# pcb_1.net
KiCad netlist of a schematic drawn in EAGLE
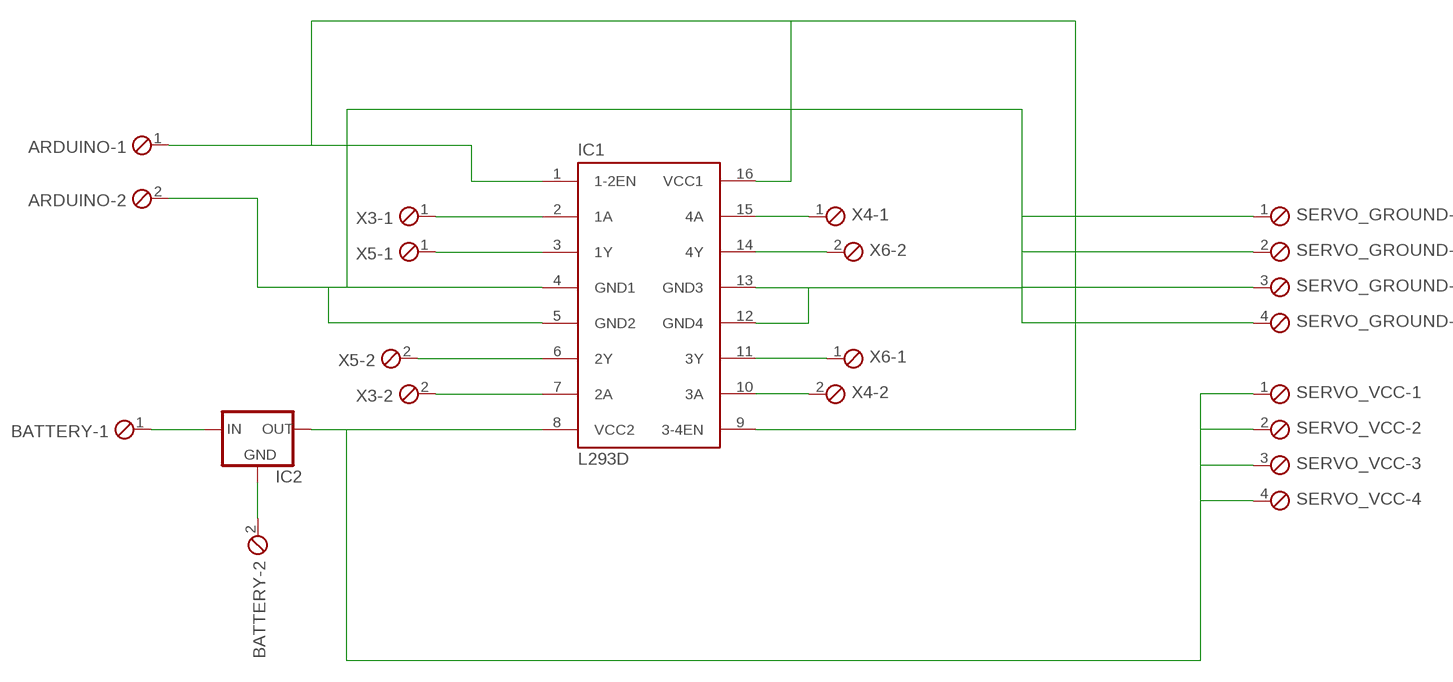
[diagram p0: schematic, sheet 1]

(export (version "E")
  (design (tool "Eeschema 10.0.6"))
  (components
    (comp (ref "ARDUINO")
      (value "MPT2")
      (footprint "eagle-import:2POL254")
      (libsource (lib "eagle-import") (part "MPT2"))
    )
    (comp (ref "BATTERY")
      (value "MPT2")
      (footprint "eagle-import:2POL254")
      (libsource (lib "eagle-import") (part "MPT2"))
    )
    (comp (ref "IC1")
      (value "L293D")
      (footprint "eagle-import:DIL16")
      (libsource (lib "eagle-import") (part "L293D"))
    )
    (comp (ref "IC2")
      (value "78MXXS")
      (footprint "eagle-import:78MXXS")
      (libsource (lib "eagle-import") (part "78MXXS"))
    )
    (comp (ref "SERVO_GROUND")
      (value "MPT4")
      (footprint "eagle-import:4POL254")
      (libsource (lib "eagle-import") (part "MPT4"))
    )
    (comp (ref "SERVO_VCC")
      (value "MPT4")
      (footprint "eagle-import:4POL254")
      (libsource (lib "eagle-import") (part "MPT4"))
    )
    (comp (ref "X3")
      (value "MPT2")
      (footprint "eagle-import:2POL254")
      (libsource (lib "eagle-import") (part "MPT2"))
    )
    (comp (ref "X4")
      (value "MPT2")
      (footprint "eagle-import:2POL254")
      (libsource (lib "eagle-import") (part "MPT2"))
    )
    (comp (ref "X5")
      (value "MPT2")
      (footprint "eagle-import:2POL254")
      (libsource (lib "eagle-import") (part "MPT2"))
    )
    (comp (ref "X6")
      (value "MPT2")
      (footprint "eagle-import:2POL254")
      (libsource (lib "eagle-import") (part "MPT2"))
    )
  )
  (nets
    (net (code "1") (name "Net-(ARDUINOB-1)") (class "Default")
      (node (ref "ARDUINO") (pin "2") (pinfunction "1_2") (pintype "passive"))
      (node (ref "IC1") (pin "12") (pinfunction "GND4_12") (pintype "power_in"))
      (node (ref "IC1") (pin "13") (pinfunction "GND3_13") (pintype "power_in"))
      (node (ref "IC1") (pin "4") (pinfunction "GND1_4") (pintype "power_in"))
      (node (ref "IC1") (pin "5") (pinfunction "GND2_5") (pintype "power_in"))
      (node (ref "SERVO_GROUND") (pin "1") (pinfunction "1_1") (pintype "passive"))
      (node (ref "SERVO_GROUND") (pin "2") (pinfunction "1_2") (pintype "passive"))
      (node (ref "SERVO_GROUND") (pin "3") (pinfunction "1_3") (pintype "passive"))
      (node (ref "SERVO_GROUND") (pin "4") (pinfunction "1_4") (pintype "passive"))
    )
    (net (code "2") (name "Net-(BATTERY-Pad1)") (class "Default")
      (node (ref "BATTERY") (pin "1") (pinfunction "1_1") (pintype "passive"))
      (node (ref "IC2") (pin "IN") (pinfunction "IN_IN") (pintype "input"))
    )
    (net (code "3") (name "Net-(BATTERYB-1)") (class "Default")
      (node (ref "BATTERY") (pin "2") (pinfunction "1_2") (pintype "passive"))
      (node (ref "IC2") (pin "GND") (pinfunction "GND_GND") (pintype "input"))
    )
    (net (code "4") (name "Net-(IC1-1-2EN)") (class "Default")
      (node (ref "ARDUINO") (pin "1") (pinfunction "1_1") (pintype "passive"))
      (node (ref "IC1") (pin "1") (pinfunction "1-2EN_1") (pintype "input"))
      (node (ref "IC1") (pin "16") (pinfunction "VCC1_16") (pintype "power_in"))
      (node (ref "IC1") (pin "9") (pinfunction "3-4EN_9") (pintype "input"))
    )
    (net (code "5") (name "Net-(IC1-1A)") (class "Default")
      (node (ref "IC1") (pin "2") (pinfunction "1A_2") (pintype "input"))
      (node (ref "X3") (pin "1") (pinfunction "1_1") (pintype "passive"))
    )
    (net (code "6") (name "Net-(IC1-1Y)") (class "Default")
      (node (ref "IC1") (pin "3") (pinfunction "1Y_3") (pintype "output"))
      (node (ref "X5") (pin "1") (pinfunction "1_1") (pintype "passive"))
    )
    (net (code "7") (name "Net-(IC1-2A)") (class "Default")
      (node (ref "IC1") (pin "7") (pinfunction "2A_7") (pintype "input"))
      (node (ref "X3") (pin "2") (pinfunction "1_2") (pintype "passive"))
    )
    (net (code "8") (name "Net-(IC1-2Y)") (class "Default")
      (node (ref "IC1") (pin "6") (pinfunction "2Y_6") (pintype "output"))
      (node (ref "X5") (pin "2") (pinfunction "1_2") (pintype "passive"))
    )
    (net (code "9") (name "Net-(IC1-3A)") (class "Default")
      (node (ref "IC1") (pin "10") (pinfunction "3A_10") (pintype "input"))
      (node (ref "X4") (pin "2") (pinfunction "1_2") (pintype "passive"))
    )
    (net (code "10") (name "Net-(IC1-3Y)") (class "Default")
      (node (ref "IC1") (pin "11") (pinfunction "3Y_11") (pintype "output"))
      (node (ref "X6") (pin "1") (pinfunction "1_1") (pintype "passive"))
    )
    (net (code "11") (name "Net-(IC1-4A)") (class "Default")
      (node (ref "IC1") (pin "15") (pinfunction "4A_15") (pintype "input"))
      (node (ref "X4") (pin "1") (pinfunction "1_1") (pintype "passive"))
    )
    (net (code "12") (name "Net-(IC1-4Y)") (class "Default")
      (node (ref "IC1") (pin "14") (pinfunction "4Y_14") (pintype "output"))
      (node (ref "X6") (pin "2") (pinfunction "1_2") (pintype "passive"))
    )
    (net (code "13") (name "Net-(IC1-VCC2)") (class "Default")
      (node (ref "IC1") (pin "8") (pinfunction "VCC2_8") (pintype "power_in"))
      (node (ref "IC2") (pin "OUT") (pinfunction "OUT_OUT") (pintype "passive"))
      (node (ref "SERVO_VCC") (pin "1") (pinfunction "1_1") (pintype "passive"))
      (node (ref "SERVO_VCC") (pin "2") (pinfunction "1_2") (pintype "passive"))
      (node (ref "SERVO_VCC") (pin "3") (pinfunction "1_3") (pintype "passive"))
      (node (ref "SERVO_VCC") (pin "4") (pinfunction "1_4") (pintype "passive"))
    )
  )
)
